# 1_Interface_QuadUART.net
KiCad netlist of a schematic drawn in Altium Designer
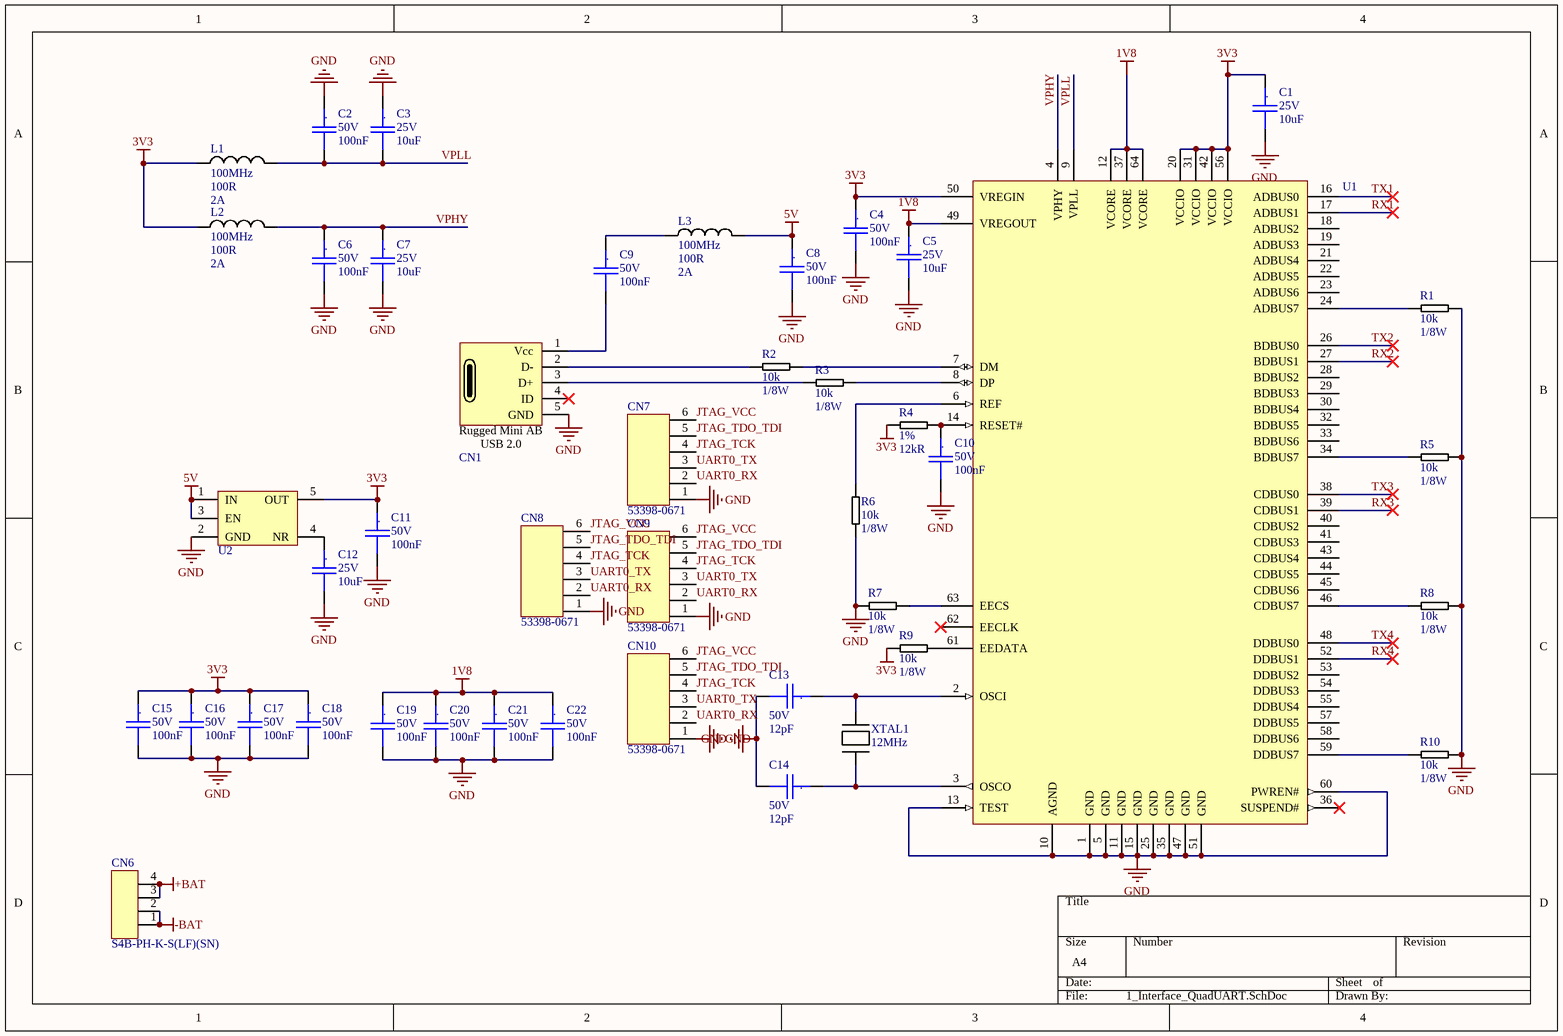
[diagram p0: 1_Interface_QuadUART.SchDoc]

(export (version "E")
  (design (tool "Eeschema 10.0.6"))
  (components
    (comp (ref "C1")
      (value "GRM31CR71E106KA12K")
      (footprint "C1206_MD")
      (description "CAP CER 10UF 25V X7R 1206")
      (fields
        (field (name "MANUFACTURER") "Murata")
        (field (name "TOLERANCE") "10%")
        (field (name "VOLTAGE") "25V")
        (field (name "CAPACITANCE") "10uF")
      )
      (libsource (lib "IB_floripasat2") (part "GRM31CR71E106KA12K"))
    )
    (comp (ref "C2")
      (value "C1608X7R1H104K080AA")
      (footprint "C0603_MD")
      (fields
        (field (name "MANUFACTURER") "TDK")
        (field (name "TOLERANCE") "10%")
        (field (name "VOLTAGE") "50V")
        (field (name "VOLTAGE RATING") "50V")
        (field (name "CAPACITANCE") "100nF")
      )
      (libsource (lib "IB_floripasat2") (part "C1608X7R1H104K080AA"))
    )
    (comp (ref "C3")
      (value "GRM31CR71E106KA12K")
      (footprint "C1206_MD")
      (description "CAP CER 10UF 25V X7R 1206")
      (fields
        (field (name "MANUFACTURER") "Murata")
        (field (name "TOLERANCE") "10%")
        (field (name "VOLTAGE") "25V")
        (field (name "CAPACITANCE") "10uF")
      )
      (libsource (lib "IB_floripasat2") (part "GRM31CR71E106KA12K"))
    )
    (comp (ref "C4")
      (value "C1608X7R1H104K080AA")
      (footprint "C0603_MD")
      (fields
        (field (name "MANUFACTURER") "TDK")
        (field (name "TOLERANCE") "10%")
        (field (name "VOLTAGE") "50V")
        (field (name "VOLTAGE RATING") "50V")
        (field (name "CAPACITANCE") "100nF")
      )
      (libsource (lib "IB_floripasat2") (part "C1608X7R1H104K080AA"))
    )
    (comp (ref "C5")
      (value "GRM31CR71E106KA12K")
      (footprint "C1206_MD")
      (description "CAP CER 10UF 25V X7R 1206")
      (fields
        (field (name "MANUFACTURER") "Murata")
        (field (name "TOLERANCE") "10%")
        (field (name "VOLTAGE") "25V")
        (field (name "CAPACITANCE") "10uF")
      )
      (libsource (lib "IB_floripasat2") (part "GRM31CR71E106KA12K"))
    )
    (comp (ref "C6")
      (value "C1608X7R1H104K080AA")
      (footprint "C0603_MD")
      (fields
        (field (name "MANUFACTURER") "TDK")
        (field (name "TOLERANCE") "10%")
        (field (name "VOLTAGE") "50V")
        (field (name "VOLTAGE RATING") "50V")
        (field (name "CAPACITANCE") "100nF")
      )
      (libsource (lib "IB_floripasat2") (part "C1608X7R1H104K080AA"))
    )
    (comp (ref "C7")
      (value "GRM31CR71E106KA12K")
      (footprint "C1206_MD")
      (description "CAP CER 10UF 25V X7R 1206")
      (fields
        (field (name "MANUFACTURER") "Murata")
        (field (name "TOLERANCE") "10%")
        (field (name "VOLTAGE") "25V")
        (field (name "CAPACITANCE") "10uF")
      )
      (libsource (lib "IB_floripasat2") (part "GRM31CR71E106KA12K"))
    )
    (comp (ref "C8")
      (value "C1608X7R1H104K080AA")
      (footprint "C0603_MD")
      (fields
        (field (name "MANUFACTURER") "TDK")
        (field (name "TOLERANCE") "10%")
        (field (name "VOLTAGE") "50V")
        (field (name "VOLTAGE RATING") "50V")
        (field (name "CAPACITANCE") "100nF")
      )
      (libsource (lib "IB_floripasat2") (part "C1608X7R1H104K080AA"))
    )
    (comp (ref "C9")
      (value "C1608X7R1H104K080AA")
      (footprint "C0603_MD")
      (fields
        (field (name "MANUFACTURER") "TDK")
        (field (name "TOLERANCE") "10%")
        (field (name "VOLTAGE") "50V")
        (field (name "VOLTAGE RATING") "50V")
        (field (name "CAPACITANCE") "100nF")
      )
      (libsource (lib "IB_floripasat2") (part "C1608X7R1H104K080AA"))
    )
    (comp (ref "C10")
      (value "C1608X7R1H104K080AA")
      (footprint "C0603_MD")
      (fields
        (field (name "MANUFACTURER") "TDK")
        (field (name "TOLERANCE") "10%")
        (field (name "VOLTAGE") "50V")
        (field (name "VOLTAGE RATING") "50V")
        (field (name "CAPACITANCE") "100nF")
      )
      (libsource (lib "IB_floripasat2") (part "C1608X7R1H104K080AA"))
    )
    (comp (ref "C11")
      (value "C1608X7R1H104K080AA")
      (footprint "C0603_MD")
      (fields
        (field (name "MANUFACTURER") "TDK")
        (field (name "TOLERANCE") "10%")
        (field (name "VOLTAGE") "50V")
        (field (name "VOLTAGE RATING") "50V")
        (field (name "CAPACITANCE") "100nF")
      )
      (libsource (lib "IB_floripasat2") (part "C1608X7R1H104K080AA"))
    )
    (comp (ref "C12")
      (value "GRM31CR71E106KA12K")
      (footprint "C1206_MD")
      (description "CAP CER 10UF 25V X7R 1206")
      (fields
        (field (name "MANUFACTURER") "Murata")
        (field (name "TOLERANCE") "10%")
        (field (name "VOLTAGE") "25V")
        (field (name "CAPACITANCE") "10uF")
      )
      (libsource (lib "IB_floripasat2") (part "GRM31CR71E106KA12K"))
    )
    (comp (ref "C13")
      (value "CL10C120JB8NNNC")
      (footprint "C0603_MD")
      (description "Cap Ceramic 12pF 50VDC C0G 5% SMD 0603 Paper T/R")
      (fields
        (field (name "MANUFACTURER") "Samsung")
        (field (name "TOLERANCE") "5%")
        (field (name "VOLTAGE") "50V")
        (field (name "CAPACITANCE") "12pF")
      )
      (libsource (lib "IB_floripasat2") (part "CL10C120JB8NNNC"))
    )
    (comp (ref "C14")
      (value "CL10C120JB8NNNC")
      (footprint "C0603_MD")
      (description "Cap Ceramic 12pF 50VDC C0G 5% SMD 0603 Paper T/R")
      (fields
        (field (name "MANUFACTURER") "Samsung")
        (field (name "TOLERANCE") "5%")
        (field (name "VOLTAGE") "50V")
        (field (name "CAPACITANCE") "12pF")
      )
      (libsource (lib "IB_floripasat2") (part "CL10C120JB8NNNC"))
    )
    (comp (ref "C15")
      (value "C1608X7R1H104K080AA")
      (footprint "C0603_MD")
      (fields
        (field (name "MANUFACTURER") "TDK")
        (field (name "TOLERANCE") "10%")
        (field (name "VOLTAGE") "50V")
        (field (name "VOLTAGE RATING") "50V")
        (field (name "CAPACITANCE") "100nF")
      )
      (libsource (lib "IB_floripasat2") (part "C1608X7R1H104K080AA"))
    )
    (comp (ref "C16")
      (value "C1608X7R1H104K080AA")
      (footprint "C0603_MD")
      (fields
        (field (name "MANUFACTURER") "TDK")
        (field (name "TOLERANCE") "10%")
        (field (name "VOLTAGE") "50V")
        (field (name "VOLTAGE RATING") "50V")
        (field (name "CAPACITANCE") "100nF")
      )
      (libsource (lib "IB_floripasat2") (part "C1608X7R1H104K080AA"))
    )
    (comp (ref "C17")
      (value "C1608X7R1H104K080AA")
      (footprint "C0603_MD")
      (fields
        (field (name "MANUFACTURER") "TDK")
        (field (name "TOLERANCE") "10%")
        (field (name "VOLTAGE") "50V")
        (field (name "VOLTAGE RATING") "50V")
        (field (name "CAPACITANCE") "100nF")
      )
      (libsource (lib "IB_floripasat2") (part "C1608X7R1H104K080AA"))
    )
    (comp (ref "C18")
      (value "C1608X7R1H104K080AA")
      (footprint "C0603_MD")
      (fields
        (field (name "MANUFACTURER") "TDK")
        (field (name "TOLERANCE") "10%")
        (field (name "VOLTAGE") "50V")
        (field (name "VOLTAGE RATING") "50V")
        (field (name "CAPACITANCE") "100nF")
      )
      (libsource (lib "IB_floripasat2") (part "C1608X7R1H104K080AA"))
    )
    (comp (ref "C19")
      (value "C1608X7R1H104K080AA")
      (footprint "C0603_MD")
      (fields
        (field (name "MANUFACTURER") "TDK")
        (field (name "TOLERANCE") "10%")
        (field (name "VOLTAGE") "50V")
        (field (name "VOLTAGE RATING") "50V")
        (field (name "CAPACITANCE") "100nF")
      )
      (libsource (lib "IB_floripasat2") (part "C1608X7R1H104K080AA"))
    )
    (comp (ref "C20")
      (value "C1608X7R1H104K080AA")
      (footprint "C0603_MD")
      (fields
        (field (name "MANUFACTURER") "TDK")
        (field (name "TOLERANCE") "10%")
        (field (name "VOLTAGE") "50V")
        (field (name "VOLTAGE RATING") "50V")
        (field (name "CAPACITANCE") "100nF")
      )
      (libsource (lib "IB_floripasat2") (part "C1608X7R1H104K080AA"))
    )
    (comp (ref "C21")
      (value "C1608X7R1H104K080AA")
      (footprint "C0603_MD")
      (fields
        (field (name "MANUFACTURER") "TDK")
        (field (name "TOLERANCE") "10%")
        (field (name "VOLTAGE") "50V")
        (field (name "VOLTAGE RATING") "50V")
        (field (name "CAPACITANCE") "100nF")
      )
      (libsource (lib "IB_floripasat2") (part "C1608X7R1H104K080AA"))
    )
    (comp (ref "C22")
      (value "C1608X7R1H104K080AA")
      (footprint "C0603_MD")
      (fields
        (field (name "MANUFACTURER") "TDK")
        (field (name "TOLERANCE") "10%")
        (field (name "VOLTAGE") "50V")
        (field (name "VOLTAGE RATING") "50V")
        (field (name "CAPACITANCE") "100nF")
      )
      (libsource (lib "IB_floripasat2") (part "C1608X7R1H104K080AA"))
    )
    (comp (ref "CN1")
      (value "MUSBR-E551-30")
      (footprint "RUGGED USB MINI AB VERTICAL")
      (description "RUGGED USB MINI AB VERTICAL")
      (fields (field (name "MANUFACTURER") "Amphenol Commercial"))
      (libsource (lib "IB_floripasat2") (part "MUSBR-E551-30"))
    )
    (comp (ref "CN6")
      (value "S4B-PH-K-S(LF)(SN)")
      (footprint "CONN HEADER R/A 4POS 2MM")
      (description "JST (JAPAN SOLDERLESS TERMINALS) - S4B-PH-K-S (LF)(SN) - CONNECTOR, HEADER, 2MM, 4 POSITION, 1ROW")
      (fields (field (name "MANUFACTURER") "JST"))
      (libsource (lib "IB_floripasat2") (part "S4B-PH-K-S(LF)(SN)"))
    )
    (comp (ref "CN7")
      (value "53398-0671")
      (footprint "PICO BLADE 0533980671")
      (description "1.25mm Pitch PicoBlade™ Header, Surface Mount, Vertical, 6 Circuits")
      (fields (field (name "MANUFACTURER") "Molex"))
      (libsource (lib "IB_floripasat2") (part "53398-0671"))
    )
    (comp (ref "CN8")
      (value "53398-0671")
      (footprint "PICO BLADE 0533980671")
      (description "1.25mm Pitch PicoBlade™ Header, Surface Mount, Vertical, 6 Circuits")
      (fields (field (name "MANUFACTURER") "Molex"))
      (libsource (lib "IB_floripasat2") (part "53398-0671"))
    )
    (comp (ref "CN9")
      (value "53398-0671")
      (footprint "PICO BLADE 0533980671")
      (description "1.25mm Pitch PicoBlade™ Header, Surface Mount, Vertical, 6 Circuits")
      (fields (field (name "MANUFACTURER") "Molex"))
      (libsource (lib "IB_floripasat2") (part "53398-0671"))
    )
    (comp (ref "CN10")
      (value "53398-0671")
      (footprint "PICO BLADE 0533980671")
      (description "1.25mm Pitch PicoBlade™ Header, Surface Mount, Vertical, 6 Circuits")
      (fields (field (name "MANUFACTURER") "Molex"))
      (libsource (lib "IB_floripasat2") (part "53398-0671"))
    )
    (comp (ref "L1")
      (value "BLM18EG101TN1D")
      (footprint "L0603")
      (description "FERRITE BEAD 100 OHM 0603 1LN")
      (fields
        (field (name "MANUFACTURER") "Murata")
        (field (name "TOLERANCE") "25%")
        (field (name "TEST FREQUENCY") "100MHz")
        (field (name "IMPEDANCE") "100R")
        (field (name "CURRENT RATING") "2A")
      )
      (libsource (lib "IB_floripasat2") (part "BLM18EG101TN1D"))
    )
    (comp (ref "L2")
      (value "BLM18EG101TN1D")
      (footprint "L0603")
      (description "FERRITE BEAD 100 OHM 0603 1LN")
      (fields
        (field (name "MANUFACTURER") "Murata")
        (field (name "TOLERANCE") "25%")
        (field (name "TEST FREQUENCY") "100MHz")
        (field (name "IMPEDANCE") "100R")
        (field (name "CURRENT RATING") "2A")
      )
      (libsource (lib "IB_floripasat2") (part "BLM18EG101TN1D"))
    )
    (comp (ref "L3")
      (value "BLM18EG101TN1D")
      (footprint "L0603")
      (description "FERRITE BEAD 100 OHM 0603 1LN")
      (fields
        (field (name "MANUFACTURER") "Murata")
        (field (name "TOLERANCE") "25%")
        (field (name "TEST FREQUENCY") "100MHz")
        (field (name "IMPEDANCE") "100R")
        (field (name "CURRENT RATING") "2A")
      )
      (libsource (lib "IB_floripasat2") (part "BLM18EG101TN1D"))
    )
    (comp (ref "R1")
      (value "10k")
      (footprint "R0805_MD")
      (description "RES 10.0K OHM 1/8W 1% 0805 SMD")
      (fields
        (field (name "MANUFACTURER") "Vishay Dale")
        (field (name "TOLERANCE") "1%")
        (field (name "POWER") "1/8W")
      )
      (libsource (lib "IB_floripasat2") (part "CRCW080510K0FKEA"))
    )
    (comp (ref "R2")
      (value "10k")
      (footprint "R0805_MD")
      (description "RES 10.0K OHM 1/8W 1% 0805 SMD")
      (fields
        (field (name "MANUFACTURER") "Vishay Dale")
        (field (name "TOLERANCE") "1%")
        (field (name "POWER") "1/8W")
      )
      (libsource (lib "IB_floripasat2") (part "CRCW080510K0FKEA"))
    )
    (comp (ref "R3")
      (value "10k")
      (footprint "R0805_MD")
      (description "RES 10.0K OHM 1/8W 1% 0805 SMD")
      (fields
        (field (name "MANUFACTURER") "Vishay Dale")
        (field (name "TOLERANCE") "1%")
        (field (name "POWER") "1/8W")
      )
      (libsource (lib "IB_floripasat2") (part "CRCW080510K0FKEA"))
    )
    (comp (ref "R4")
      (value "RMCF0805FT12K0")
      (footprint "R0805_MD")
      (description "Resistor, SMT, 0805, 12K Ohm, +/-1%, +/-100ppm, Thk Film, T/R Marked")
      (fields
        (field (name "MANUFACTURER") "Stackpole Electronics")
        (field (name "TOLERANCE") "1%")
        (field (name "RESISTANCE") "12kR")
      )
      (libsource (lib "IB_floripasat2") (part "RMCF0805FT12K0"))
    )
    (comp (ref "R5")
      (value "10k")
      (footprint "R0805_MD")
      (description "RES 10.0K OHM 1/8W 1% 0805 SMD")
      (fields
        (field (name "MANUFACTURER") "Vishay Dale")
        (field (name "TOLERANCE") "1%")
        (field (name "POWER") "1/8W")
      )
      (libsource (lib "IB_floripasat2") (part "CRCW080510K0FKEA"))
    )
    (comp (ref "R6")
      (value "10k")
      (footprint "R0805_MD")
      (description "RES 10.0K OHM 1/8W 1% 0805 SMD")
      (fields
        (field (name "MANUFACTURER") "Vishay Dale")
        (field (name "TOLERANCE") "1%")
        (field (name "POWER") "1/8W")
      )
      (libsource (lib "IB_floripasat2") (part "CRCW080510K0FKEA"))
    )
    (comp (ref "R7")
      (value "10k")
      (footprint "R0805_MD")
      (description "RES 10.0K OHM 1/8W 1% 0805 SMD")
      (fields
        (field (name "MANUFACTURER") "Vishay Dale")
        (field (name "TOLERANCE") "1%")
        (field (name "POWER") "1/8W")
      )
      (libsource (lib "IB_floripasat2") (part "CRCW080510K0FKEA"))
    )
    (comp (ref "R8")
      (value "10k")
      (footprint "R0805_MD")
      (description "RES 10.0K OHM 1/8W 1% 0805 SMD")
      (fields
        (field (name "MANUFACTURER") "Vishay Dale")
        (field (name "TOLERANCE") "1%")
        (field (name "POWER") "1/8W")
      )
      (libsource (lib "IB_floripasat2") (part "CRCW080510K0FKEA"))
    )
    (comp (ref "R9")
      (value "10k")
      (footprint "R0805_MD")
      (description "RES 10.0K OHM 1/8W 1% 0805 SMD")
      (fields
        (field (name "MANUFACTURER") "Vishay Dale")
        (field (name "TOLERANCE") "1%")
        (field (name "POWER") "1/8W")
      )
      (libsource (lib "IB_floripasat2") (part "CRCW080510K0FKEA"))
    )
    (comp (ref "R10")
      (value "10k")
      (footprint "R0805_MD")
      (description "RES 10.0K OHM 1/8W 1% 0805 SMD")
      (fields
        (field (name "MANUFACTURER") "Vishay Dale")
        (field (name "TOLERANCE") "1%")
        (field (name "POWER") "1/8W")
      )
      (libsource (lib "IB_floripasat2") (part "CRCW080510K0FKEA"))
    )
    (comp (ref "U1")
      (value "IC USB HS QUAD UART")
      (footprint "LQFP-64")
      (description "FTDI - FT4232HL-REEL - USB-UART/MPSSE, 4232, QUAD, 64LQFP")
      (fields (field (name "MANUFACTURER") "FTDI") (field (name "MANUFACTURER PART NUMBER") "FT4232HL-REEL"))
      (libsource (lib "IB_floripasat2") (part "FT4232HL-REEL"))
    )
    (comp (ref "U2")
      (value "TPS79333DBVR")
      (footprint "SOT23-5")
      (description "TEXAS INSTRUMENTS - TPS79333DBVR - IC, V REG, LINEAR, 0.2A, SOT-23-5")
      (fields (field (name "MANUFACTURER") "Texas Instruments"))
      (libsource (lib "IB_floripasat2") (part "TPS79333DBVR"))
    )
    (comp (ref "XTAL1")
      (value "AA-12.000MAGE-T")
      (footprint "TXC 7A Series")
      (description "Crystals 12.000MHz 30ppm 12pF -40C to 85C")
      (fields
        (field (name "MANUFACTURER") "TXC")
        (field (name "TOLERANCE") "30ppm")
        (field (name "FREQUENCY") "12MHz")
      )
      (libsource (lib "IB_floripasat2") (part "AA-12.000MAGE-T"))
    )
  )
  (nets
    (net (code "1") (name "+BAT") (class "Default")
      (node (ref "CN6") (pin "3") (pintype "passive"))
      (node (ref "CN6") (pin "4") (pintype "passive"))
    )
    (net (code "2") (name "-BAT") (class "Default")
      (node (ref "CN6") (pin "1") (pintype "passive"))
      (node (ref "CN6") (pin "2") (pintype "passive"))
    )
    (net (code "3") (name "/JTAG_TCK") (class "Default")
      (node (ref "CN10") (pin "4") (pintype "passive"))
      (node (ref "CN7") (pin "4") (pintype "passive"))
      (node (ref "CN8") (pin "4") (pintype "passive"))
      (node (ref "CN9") (pin "4") (pintype "passive"))
    )
    (net (code "4") (name "/JTAG_TDO_TDI") (class "Default")
      (node (ref "CN10") (pin "5") (pintype "passive"))
      (node (ref "CN7") (pin "5") (pintype "passive"))
      (node (ref "CN8") (pin "5") (pintype "passive"))
      (node (ref "CN9") (pin "5") (pintype "passive"))
    )
    (net (code "5") (name "/JTAG_VCC") (class "Default")
      (node (ref "CN10") (pin "6") (pintype "passive"))
      (node (ref "CN7") (pin "6") (pintype "passive"))
      (node (ref "CN8") (pin "6") (pintype "passive"))
      (node (ref "CN9") (pin "6") (pintype "passive"))
    )
    (net (code "6") (name "/RX1") (class "Default")
      (node (ref "U1") (pin "17") (pinfunction "ADBUS1_17") (pintype "passive+no_connect"))
    )
    (net (code "7") (name "/RX2") (class "Default")
      (node (ref "U1") (pin "27") (pinfunction "BDBUS1_27") (pintype "passive+no_connect"))
    )
    (net (code "8") (name "/RX3") (class "Default")
      (node (ref "U1") (pin "39") (pinfunction "CDBUS1_39") (pintype "passive+no_connect"))
    )
    (net (code "9") (name "/RX4") (class "Default")
      (node (ref "U1") (pin "52") (pinfunction "DDBUS1_52") (pintype "passive+no_connect"))
    )
    (net (code "10") (name "/TX1") (class "Default")
      (node (ref "U1") (pin "16") (pinfunction "ADBUS0_16") (pintype "passive+no_connect"))
    )
    (net (code "11") (name "/TX2") (class "Default")
      (node (ref "U1") (pin "26") (pinfunction "BDBUS0_26") (pintype "passive+no_connect"))
    )
    (net (code "12") (name "/TX3") (class "Default")
      (node (ref "U1") (pin "38") (pinfunction "CDBUS0_38") (pintype "passive+no_connect"))
    )
    (net (code "13") (name "/TX4") (class "Default")
      (node (ref "U1") (pin "48") (pinfunction "DDBUS0_48") (pintype "passive+no_connect"))
    )
    (net (code "14") (name "/UART0_RX") (class "Default")
      (node (ref "CN10") (pin "2") (pintype "passive"))
      (node (ref "CN7") (pin "2") (pintype "passive"))
      (node (ref "CN8") (pin "2") (pintype "passive"))
      (node (ref "CN9") (pin "2") (pintype "passive"))
    )
    (net (code "15") (name "/UART0_TX") (class "Default")
      (node (ref "CN10") (pin "3") (pintype "passive"))
      (node (ref "CN7") (pin "3") (pintype "passive"))
      (node (ref "CN8") (pin "3") (pintype "passive"))
      (node (ref "CN9") (pin "3") (pintype "passive"))
    )
    (net (code "16") (name "/VPHY") (class "Default")
      (node (ref "C6") (pin "1") (pinfunction "1_1") (pintype "passive"))
      (node (ref "C7") (pin "1") (pinfunction "1_1") (pintype "passive"))
      (node (ref "L2") (pin "2") (pinfunction "2_2") (pintype "passive"))
      (node (ref "U1") (pin "4") (pinfunction "VPHY_4") (pintype "power_in"))
    )
    (net (code "17") (name "/VPLL") (class "Default")
      (node (ref "C2") (pin "2") (pinfunction "2_2") (pintype "passive"))
      (node (ref "C3") (pin "2") (pinfunction "2_2") (pintype "passive"))
      (node (ref "L1") (pin "2") (pinfunction "2_2") (pintype "passive"))
      (node (ref "U1") (pin "9") (pinfunction "VPLL_9") (pintype "power_in"))
    )
    (net (code "18") (name "1V8") (class "Default")
      (node (ref "C19") (pin "1") (pinfunction "1_1") (pintype "passive"))
      (node (ref "C20") (pin "1") (pinfunction "1_1") (pintype "passive"))
      (node (ref "C21") (pin "1") (pinfunction "1_1") (pintype "passive"))
      (node (ref "C22") (pin "1") (pinfunction "1_1") (pintype "passive"))
      (node (ref "C5") (pin "1") (pinfunction "1_1") (pintype "passive"))
      (node (ref "U1") (pin "12") (pinfunction "VCORE_12") (pintype "power_in"))
      (node (ref "U1") (pin "37") (pinfunction "VCORE_37") (pintype "power_in"))
      (node (ref "U1") (pin "49") (pinfunction "VREGOUT_49") (pintype "passive"))
      (node (ref "U1") (pin "64") (pinfunction "VCORE_64") (pintype "power_in"))
    )
    (net (code "19") (name "3V3") (class "Default")
      (node (ref "C1") (pin "1") (pinfunction "1_1") (pintype "passive"))
      (node (ref "C11") (pin "1") (pinfunction "1_1") (pintype "passive"))
      (node (ref "C15") (pin "1") (pinfunction "1_1") (pintype "passive"))
      (node (ref "C16") (pin "1") (pinfunction "1_1") (pintype "passive"))
      (node (ref "C17") (pin "1") (pinfunction "1_1") (pintype "passive"))
      (node (ref "C18") (pin "1") (pinfunction "1_1") (pintype "passive"))
      (node (ref "C4") (pin "1") (pinfunction "1_1") (pintype "passive"))
      (node (ref "L1") (pin "1") (pinfunction "1_1") (pintype "passive"))
      (node (ref "L2") (pin "1") (pinfunction "1_1") (pintype "passive"))
      (node (ref "R4") (pin "1") (pinfunction "1_1") (pintype "passive"))
      (node (ref "R9") (pin "1") (pinfunction "1_1") (pintype "passive"))
      (node (ref "U1") (pin "20") (pinfunction "VCCIO_20") (pintype "power_in"))
      (node (ref "U1") (pin "31") (pinfunction "VCCIO_31") (pintype "power_in"))
      (node (ref "U1") (pin "42") (pinfunction "VCCIO_42") (pintype "power_in"))
      (node (ref "U1") (pin "50") (pinfunction "VREGIN_50") (pintype "passive"))
      (node (ref "U1") (pin "56") (pinfunction "VCCIO_56") (pintype "power_in"))
      (node (ref "U2") (pin "5") (pinfunction "OUT_5") (pintype "passive"))
    )
    (net (code "20") (name "5V") (class "Default")
      (node (ref "C8") (pin "1") (pinfunction "1_1") (pintype "passive"))
      (node (ref "L3") (pin "2") (pinfunction "2_2") (pintype "passive"))
      (node (ref "U2") (pin "1") (pinfunction "IN_1") (pintype "passive"))
      (node (ref "U2") (pin "3") (pinfunction "EN_3") (pintype "passive"))
    )
    (net (code "21") (name "GND") (class "Default")
      (node (ref "C1") (pin "2") (pinfunction "2_2") (pintype "passive"))
      (node (ref "C10") (pin "2") (pinfunction "2_2") (pintype "passive"))
      (node (ref "C11") (pin "2") (pinfunction "2_2") (pintype "passive"))
      (node (ref "C12") (pin "2") (pinfunction "2_2") (pintype "passive"))
      (node (ref "C13") (pin "2") (pinfunction "2_2") (pintype "passive"))
      (node (ref "C14") (pin "2") (pinfunction "2_2") (pintype "passive"))
      (node (ref "C15") (pin "2") (pinfunction "2_2") (pintype "passive"))
      (node (ref "C16") (pin "2") (pinfunction "2_2") (pintype "passive"))
      (node (ref "C17") (pin "2") (pinfunction "2_2") (pintype "passive"))
      (node (ref "C18") (pin "2") (pinfunction "2_2") (pintype "passive"))
      (node (ref "C19") (pin "2") (pinfunction "2_2") (pintype "passive"))
      (node (ref "C2") (pin "1") (pinfunction "1_1") (pintype "passive"))
      (node (ref "C20") (pin "2") (pinfunction "2_2") (pintype "passive"))
      (node (ref "C21") (pin "2") (pinfunction "2_2") (pintype "passive"))
      (node (ref "C22") (pin "2") (pinfunction "2_2") (pintype "passive"))
      (node (ref "C3") (pin "1") (pinfunction "1_1") (pintype "passive"))
      (node (ref "C4") (pin "2") (pinfunction "2_2") (pintype "passive"))
      (node (ref "C5") (pin "2") (pinfunction "2_2") (pintype "passive"))
      (node (ref "C6") (pin "2") (pinfunction "2_2") (pintype "passive"))
      (node (ref "C7") (pin "2") (pinfunction "2_2") (pintype "passive"))
      (node (ref "C8") (pin "2") (pinfunction "2_2") (pintype "passive"))
      (node (ref "CN1") (pin "5") (pinfunction "GND_5") (pintype "passive"))
      (node (ref "CN10") (pin "1") (pintype "passive"))
      (node (ref "CN7") (pin "1") (pintype "passive"))
      (node (ref "CN8") (pin "1") (pintype "passive"))
      (node (ref "CN9") (pin "1") (pintype "passive"))
      (node (ref "R1") (pin "2") (pinfunction "2_2") (pintype "passive"))
      (node (ref "R10") (pin "2") (pinfunction "2_2") (pintype "passive"))
      (node (ref "R5") (pin "2") (pinfunction "2_2") (pintype "passive"))
      (node (ref "R6") (pin "1") (pinfunction "1_1") (pintype "passive"))
      (node (ref "R7") (pin "1") (pinfunction "1_1") (pintype "passive"))
      (node (ref "R8") (pin "2") (pinfunction "2_2") (pintype "passive"))
      (node (ref "U1") (pin "1") (pinfunction "GND_1") (pintype "passive"))
      (node (ref "U1") (pin "10") (pinfunction "AGND_10") (pintype "passive"))
      (node (ref "U1") (pin "11") (pinfunction "GND_11") (pintype "passive"))
      (node (ref "U1") (pin "13") (pinfunction "TEST_13") (pintype "input"))
      (node (ref "U1") (pin "15") (pinfunction "GND_15") (pintype "passive"))
      (node (ref "U1") (pin "25") (pinfunction "GND_25") (pintype "passive"))
      (node (ref "U1") (pin "35") (pinfunction "GND_35") (pintype "passive"))
      (node (ref "U1") (pin "47") (pinfunction "GND_47") (pintype "passive"))
      (node (ref "U1") (pin "5") (pinfunction "GND_5") (pintype "passive"))
      (node (ref "U1") (pin "51") (pinfunction "GND_51") (pintype "passive"))
      (node (ref "U1") (pin "60") (pinfunction "PWREN#_60") (pintype "output"))
      (node (ref "U2") (pin "2") (pinfunction "GND_2") (pintype "passive"))
    )
    (net (code "22") (name "Net-(C9-Pad1)") (class "Default")
      (node (ref "C9") (pin "1") (pinfunction "1_1") (pintype "passive"))
      (node (ref "L3") (pin "1") (pinfunction "1_1") (pintype "passive"))
    )
    (net (code "23") (name "Net-(CN1-D+)") (class "Default")
      (node (ref "CN1") (pin "3") (pinfunction "D+_3") (pintype "passive"))
      (node (ref "R3") (pin "1") (pinfunction "1_1") (pintype "passive"))
    )
    (net (code "24") (name "Net-(CN1-D-)") (class "Default")
      (node (ref "CN1") (pin "2") (pinfunction "D-_2") (pintype "passive"))
      (node (ref "R2") (pin "1") (pinfunction "1_1") (pintype "passive"))
    )
    (net (code "25") (name "Net-(CN1-Vcc)") (class "Default")
      (node (ref "C9") (pin "2") (pinfunction "2_2") (pintype "passive"))
      (node (ref "CN1") (pin "1") (pinfunction "Vcc_1") (pintype "passive"))
    )
    (net (code "26") (name "Net-(U1-ADBUS7)") (class "Default")
      (node (ref "R1") (pin "1") (pinfunction "1_1") (pintype "passive"))
      (node (ref "U1") (pin "24") (pinfunction "ADBUS7_24") (pintype "passive"))
    )
    (net (code "27") (name "Net-(U1-BDBUS7)") (class "Default")
      (node (ref "R5") (pin "1") (pinfunction "1_1") (pintype "passive"))
      (node (ref "U1") (pin "34") (pinfunction "BDBUS7_34") (pintype "passive"))
    )
    (net (code "28") (name "Net-(U1-CDBUS7)") (class "Default")
      (node (ref "R8") (pin "1") (pinfunction "1_1") (pintype "passive"))
      (node (ref "U1") (pin "46") (pinfunction "CDBUS7_46") (pintype "passive"))
    )
    (net (code "29") (name "Net-(U1-DDBUS7)") (class "Default")
      (node (ref "R10") (pin "1") (pinfunction "1_1") (pintype "passive"))
      (node (ref "U1") (pin "59") (pinfunction "DDBUS7_59") (pintype "passive"))
    )
    (net (code "30") (name "Net-(U1-DM)") (class "Default")
      (node (ref "R2") (pin "2") (pinfunction "2_2") (pintype "passive"))
      (node (ref "U1") (pin "7") (pinfunction "DM_7") (pintype "bidirectional"))
    )
    (net (code "31") (name "Net-(U1-DP)") (class "Default")
      (node (ref "R3") (pin "2") (pinfunction "2_2") (pintype "passive"))
      (node (ref "U1") (pin "8") (pinfunction "DP_8") (pintype "bidirectional"))
    )
    (net (code "32") (name "Net-(U1-EECS)") (class "Default")
      (node (ref "R7") (pin "2") (pinfunction "2_2") (pintype "passive"))
      (node (ref "U1") (pin "63") (pinfunction "EECS_63") (pintype "passive"))
    )
    (net (code "33") (name "Net-(U1-EEDATA)") (class "Default")
      (node (ref "R9") (pin "2") (pinfunction "2_2") (pintype "passive"))
      (node (ref "U1") (pin "61") (pinfunction "EEDATA_61") (pintype "passive"))
    )
    (net (code "34") (name "Net-(U1-OSCI)") (class "Default")
      (node (ref "C13") (pin "1") (pinfunction "1_1") (pintype "passive"))
      (node (ref "U1") (pin "2") (pinfunction "OSCI_2") (pintype "input"))
      (node (ref "XTAL1") (pin "1") (pinfunction "1_1") (pintype "passive"))
    )
    (net (code "35") (name "Net-(U1-OSCO)") (class "Default")
      (node (ref "C14") (pin "1") (pinfunction "1_1") (pintype "passive"))
      (node (ref "U1") (pin "3") (pinfunction "OSCO_3") (pintype "output"))
      (node (ref "XTAL1") (pin "2") (pinfunction "2_2") (pintype "passive"))
    )
    (net (code "36") (name "Net-(U1-REF)") (class "Default")
      (node (ref "R6") (pin "2") (pinfunction "2_2") (pintype "passive"))
      (node (ref "U1") (pin "6") (pinfunction "REF_6") (pintype "input"))
    )
    (net (code "37") (name "Net-(U1-RESET#)") (class "Default")
      (node (ref "C10") (pin "1") (pinfunction "1_1") (pintype "passive"))
      (node (ref "R4") (pin "2") (pinfunction "2_2") (pintype "passive"))
      (node (ref "U1") (pin "14") (pinfunction "RESET#_14") (pintype "input"))
    )
    (net (code "38") (name "Net-(U2-NR)") (class "Default")
      (node (ref "C12") (pin "1") (pinfunction "1_1") (pintype "passive"))
      (node (ref "U2") (pin "4") (pinfunction "NR_4") (pintype "passive"))
    )
    (net (code "39") (name "unconnected-(CN1-ID-Pad4)") (class "Default")
      (node (ref "CN1") (pin "4") (pinfunction "ID_4") (pintype "passive+no_connect"))
    )
    (net (code "40") (name "unconnected-(U1-ADBUS2-Pad18)") (class "Default")
      (node (ref "U1") (pin "18") (pinfunction "ADBUS2_18") (pintype "passive"))
    )
    (net (code "41") (name "unconnected-(U1-ADBUS3-Pad19)") (class "Default")
      (node (ref "U1") (pin "19") (pinfunction "ADBUS3_19") (pintype "passive"))
    )
    (net (code "42") (name "unconnected-(U1-ADBUS4-Pad21)") (class "Default")
      (node (ref "U1") (pin "21") (pinfunction "ADBUS4_21") (pintype "passive"))
    )
    (net (code "43") (name "unconnected-(U1-ADBUS5-Pad22)") (class "Default")
      (node (ref "U1") (pin "22") (pinfunction "ADBUS5_22") (pintype "passive"))
    )
    (net (code "44") (name "unconnected-(U1-ADBUS6-Pad23)") (class "Default")
      (node (ref "U1") (pin "23") (pinfunction "ADBUS6_23") (pintype "passive"))
    )
    (net (code "45") (name "unconnected-(U1-BDBUS2-Pad28)") (class "Default")
      (node (ref "U1") (pin "28") (pinfunction "BDBUS2_28") (pintype "passive"))
    )
    (net (code "46") (name "unconnected-(U1-BDBUS3-Pad29)") (class "Default")
      (node (ref "U1") (pin "29") (pinfunction "BDBUS3_29") (pintype "passive"))
    )
    (net (code "47") (name "unconnected-(U1-BDBUS4-Pad30)") (class "Default")
      (node (ref "U1") (pin "30") (pinfunction "BDBUS4_30") (pintype "passive"))
    )
    (net (code "48") (name "unconnected-(U1-BDBUS5-Pad32)") (class "Default")
      (node (ref "U1") (pin "32") (pinfunction "BDBUS5_32") (pintype "passive"))
    )
    (net (code "49") (name "unconnected-(U1-BDBUS6-Pad33)") (class "Default")
      (node (ref "U1") (pin "33") (pinfunction "BDBUS6_33") (pintype "passive"))
    )
    (net (code "50") (name "unconnected-(U1-CDBUS2-Pad40)") (class "Default")
      (node (ref "U1") (pin "40") (pinfunction "CDBUS2_40") (pintype "passive"))
    )
    (net (code "51") (name "unconnected-(U1-CDBUS3-Pad41)") (class "Default")
      (node (ref "U1") (pin "41") (pinfunction "CDBUS3_41") (pintype "passive"))
    )
    (net (code "52") (name "unconnected-(U1-CDBUS4-Pad43)") (class "Default")
      (node (ref "U1") (pin "43") (pinfunction "CDBUS4_43") (pintype "passive"))
    )
    (net (code "53") (name "unconnected-(U1-CDBUS5-Pad44)") (class "Default")
      (node (ref "U1") (pin "44") (pinfunction "CDBUS5_44") (pintype "passive"))
    )
    (net (code "54") (name "unconnected-(U1-CDBUS6-Pad45)") (class "Default")
      (node (ref "U1") (pin "45") (pinfunction "CDBUS6_45") (pintype "passive"))
    )
    (net (code "55") (name "unconnected-(U1-DDBUS2-Pad53)") (class "Default")
      (node (ref "U1") (pin "53") (pinfunction "DDBUS2_53") (pintype "passive"))
    )
    (net (code "56") (name "unconnected-(U1-DDBUS3-Pad54)") (class "Default")
      (node (ref "U1") (pin "54") (pinfunction "DDBUS3_54") (pintype "passive"))
    )
    (net (code "57") (name "unconnected-(U1-DDBUS4-Pad55)") (class "Default")
      (node (ref "U1") (pin "55") (pinfunction "DDBUS4_55") (pintype "passive"))
    )
    (net (code "58") (name "unconnected-(U1-DDBUS5-Pad57)") (class "Default")
      (node (ref "U1") (pin "57") (pinfunction "DDBUS5_57") (pintype "passive"))
    )
    (net (code "59") (name "unconnected-(U1-DDBUS6-Pad58)") (class "Default")
      (node (ref "U1") (pin "58") (pinfunction "DDBUS6_58") (pintype "passive"))
    )
    (net (code "60") (name "unconnected-(U1-EECLK-Pad62)") (class "Default")
      (node (ref "U1") (pin "62") (pinfunction "EECLK_62") (pintype "passive+no_connect"))
    )
    (net (code "61") (name "unconnected-(U1-SUSPEND#-Pad36)") (class "Default")
      (node (ref "U1") (pin "36") (pinfunction "SUSPEND#_36") (pintype "output+no_connect"))
    )
  )
)
